# LiPo_1S_Protection_Circuit.net
KiCad netlist of a schematic drawn in Altium Designer
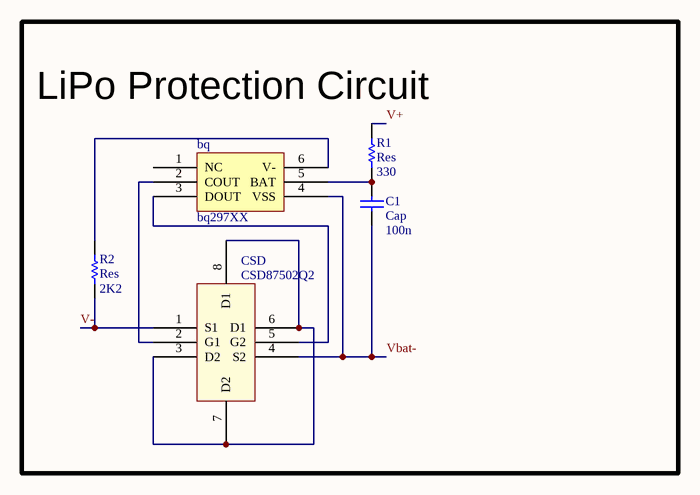
[diagram p0: LiPo_1S_Protection_Circuit.SchDoc]

(export (version "E")
  (design (tool "Eeschema 10.0.6"))
  (components
    (comp (ref "bq")
      (value "bq297XX")
      (footprint "bq297xx")
      (libsource (lib "LiPo_1S_Protection_Circuit") (part "bq297XX"))
    )
    (comp (ref "C1")
      (value "Cap")
      (footprint "0603 Cap")
      (fields (field (name "ALTIUM_VALUE") "100n"))
      (libsource (lib "B105rlc") (part "Cap"))
    )
    (comp (ref "CSD")
      (value "CSD87502Q2")
      (footprint "CSD87502Q2")
      (libsource (lib "LiPo_1S_Protection_Circuit") (part "CSD87502Q2"))
    )
    (comp (ref "R1")
      (value "Res")
      (footprint "0603 Res")
      (fields (field (name "ALTIUM_VALUE") "330"))
      (libsource (lib "B105rlc") (part "Res"))
    )
    (comp (ref "R2")
      (value "Res")
      (footprint "0603 Res")
      (fields (field (name "ALTIUM_VALUE") "2K2"))
      (libsource (lib "B105rlc") (part "Res"))
    )
  )
  (nets
    (net (code "1") (name "/V+") (class "Default")
      (node (ref "R1") (pin "2") (pinfunction "2_2") (pintype "passive"))
    )
    (net (code "2") (name "/V-") (class "Default")
      (node (ref "CSD") (pin "1") (pinfunction "S1_1") (pintype "passive"))
      (node (ref "R2") (pin "1") (pinfunction "1_1") (pintype "passive"))
    )
    (net (code "3") (name "/Vbat-") (class "Default")
      (node (ref "C1") (pin "1") (pinfunction "1_1") (pintype "passive"))
      (node (ref "CSD") (pin "4") (pinfunction "S2_4") (pintype "passive"))
      (node (ref "bq") (pin "4") (pinfunction "VSS_4") (pintype "passive"))
    )
    (net (code "4") (name "Net-(CSD-D1-Pad6)") (class "Default")
      (node (ref "CSD") (pin "3") (pinfunction "D2_3") (pintype "passive"))
      (node (ref "CSD") (pin "6") (pinfunction "D1_6") (pintype "passive"))
      (node (ref "CSD") (pin "7") (pinfunction "D2_7") (pintype "passive"))
      (node (ref "CSD") (pin "8") (pinfunction "D1_8") (pintype "passive"))
    )
    (net (code "5") (name "Net-(CSD-G1)") (class "Default")
      (node (ref "CSD") (pin "2") (pinfunction "G1_2") (pintype "passive"))
      (node (ref "bq") (pin "2") (pinfunction "COUT_2") (pintype "passive"))
    )
    (net (code "6") (name "Net-(CSD-G2)") (class "Default")
      (node (ref "CSD") (pin "5") (pinfunction "G2_5") (pintype "passive"))
      (node (ref "bq") (pin "3") (pinfunction "DOUT_3") (pintype "passive"))
    )
    (net (code "7") (name "Net-(bq-BAT)") (class "Default")
      (node (ref "C1") (pin "2") (pinfunction "2_2") (pintype "passive"))
      (node (ref "R1") (pin "1") (pinfunction "1_1") (pintype "passive"))
      (node (ref "bq") (pin "5") (pinfunction "BAT_5") (pintype "passive"))
    )
    (net (code "8") (name "Net-(bq-V-)") (class "Default")
      (node (ref "R2") (pin "2") (pinfunction "2_2") (pintype "passive"))
      (node (ref "bq") (pin "6") (pinfunction "V-_6") (pintype "passive"))
    )
    (net (code "9") (name "unconnected-(bq-NC-Pad1)") (class "Default")
      (node (ref "bq") (pin "1") (pinfunction "NC_1") (pintype "passive"))
    )
  )
)
